# test1.net
KiCad netlist of a schematic drawn in EAGLE
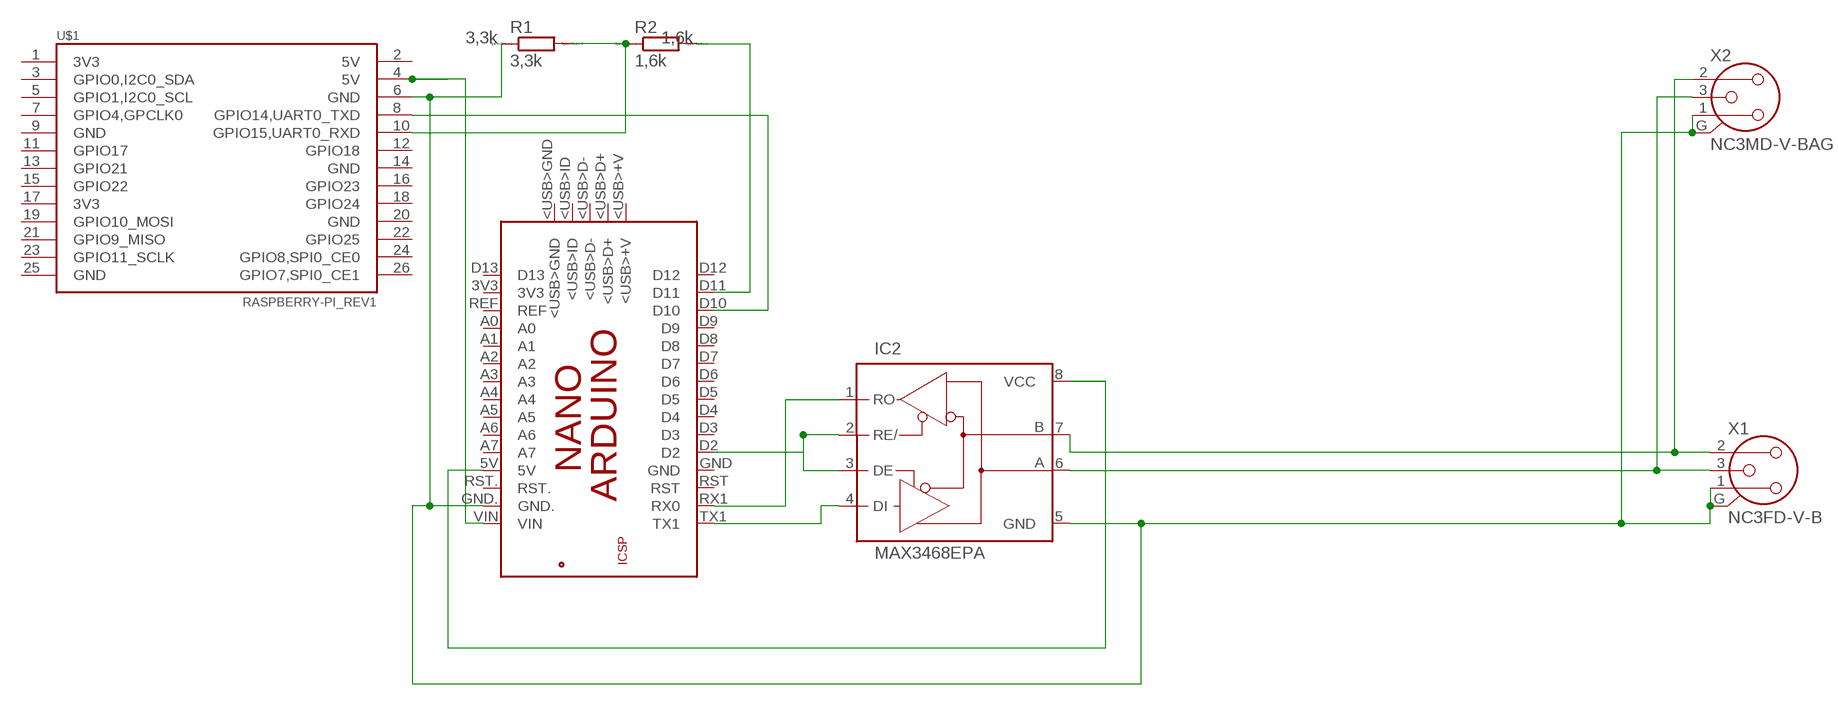
[diagram p0: schematic, sheet 1]

(export (version "E")
  (design (tool "Eeschema 10.0.6"))
  (components
    (comp (ref "IC2")
      (value "MAX3468EPA")
      (footprint "eagle-import:DIL08")
      (fields (field (name "MPN") "MAX3468EPA+"))
      (libsource (lib "eagle-import") (part "MAX34PA68E"))
    )
    (comp (ref "PCB1")
      (value "ARDUINO_NANO")
      (footprint "eagle-import:ARDUINO_NANO")
      (libsource (lib "eagle-import") (part "ARDUINO_NANO"))
    )
    (comp (ref "R1")
      (value "3,3k")
      (footprint "eagle-import:0204_7")
      (fields (field (name "SPICEMODEL") "NONE") (field (name "SPICEMODEL_1") "3,3k"))
      (libsource (lib "eagle-import") (part "R0204/7"))
    )
    (comp (ref "R2")
      (value "1,6k")
      (footprint "eagle-import:0204_7")
      (fields (field (name "SPICEMODEL") "NONE") (field (name "SPICEMODEL_1") "1,6k"))
      (libsource (lib "eagle-import") (part "R0204/7"))
    )
    (comp (ref "U$1")
      (value "RASPBERRY-PI_REV1")
      (footprint "eagle-import:RASPBERRY-PI_REV1")
      (libsource (lib "eagle-import") (part "RASPBERRY-PI_REV1"))
    )
    (comp (ref "X1")
      (value "NC3FD-V-B")
      (footprint "eagle-import:NC3FD-V-B")
      (fields (field (name "MF") "NEUTRIK"))
      (libsource (lib "eagle-import") (part "NC3FD-V-B"))
    )
    (comp (ref "X2")
      (value "NC3MD-V-BAG")
      (footprint "eagle-import:NC3MD-V-BAG")
      (fields (field (name "MF") "NEUTRIK"))
      (libsource (lib "eagle-import") (part "NC3MD-V-BAG"))
    )
  )
  (nets
    (net (code "1") (name "Net-(IC2-A)") (class "Default")
      (node (ref "IC2") (pin "6") (pinfunction "A_6") (pintype "passive"))
      (node (ref "X1") (pin "3") (pinfunction "3_3") (pintype "passive"))
      (node (ref "X2") (pin "3") (pinfunction "3_3") (pintype "passive"))
    )
    (net (code "2") (name "Net-(IC2-B)") (class "Default")
      (node (ref "IC2") (pin "7") (pinfunction "B_7") (pintype "passive"))
      (node (ref "X1") (pin "2") (pinfunction "1_2") (pintype "passive"))
      (node (ref "X2") (pin "2") (pinfunction "1_2") (pintype "passive"))
    )
    (net (code "3") (name "Net-(IC2-DE)") (class "Default")
      (node (ref "IC2") (pin "2") (pinfunction "RE/_2") (pintype "input"))
      (node (ref "IC2") (pin "3") (pinfunction "DE_3") (pintype "input"))
      (node (ref "PCB1") (pin "D2") (pinfunction "D2_D2") (pintype "bidirectional"))
    )
    (net (code "4") (name "Net-(IC2-DI)") (class "Default")
      (node (ref "IC2") (pin "4") (pinfunction "DI_4") (pintype "input"))
      (node (ref "PCB1") (pin "TX1") (pinfunction "TX1_TX1") (pintype "bidirectional"))
    )
    (net (code "5") (name "Net-(IC2-GND)") (class "Default")
      (node (ref "IC2") (pin "5") (pinfunction "GND_5") (pintype "power_in"))
      (node (ref "PCB1") (pin "GND.") (pinfunction "GND._GND.") (pintype "bidirectional"))
      (node (ref "R1") (pin "1") (pinfunction "1_1") (pintype "passive"))
      (node (ref "U$1") (pin "6") (pinfunction "GND_6") (pintype "bidirectional"))
      (node (ref "X1") (pin "1") (pinfunction "2_1") (pintype "passive"))
      (node (ref "X1") (pin "G") (pinfunction "G_G") (pintype "passive"))
      (node (ref "X2") (pin "1") (pinfunction "2_1") (pintype "passive"))
      (node (ref "X2") (pin "G") (pinfunction "G_G") (pintype "passive"))
    )
    (net (code "6") (name "Net-(IC2-RO)") (class "Default")
      (node (ref "IC2") (pin "1") (pinfunction "RO_1") (pintype "output"))
      (node (ref "PCB1") (pin "RX1") (pinfunction "RX0_RX1") (pintype "bidirectional"))
    )
    (net (code "7") (name "Net-(IC2-VCC)") (class "Default")
      (node (ref "IC2") (pin "8") (pinfunction "VCC_8") (pintype "power_in"))
      (node (ref "PCB1") (pin "5V") (pinfunction "5V_5V") (pintype "bidirectional"))
    )
    (net (code "8") (name "Net-(PCB1-PadD11)") (class "Default")
      (node (ref "PCB1") (pin "D11") (pinfunction "D11_D11") (pintype "bidirectional"))
      (node (ref "R2") (pin "2") (pinfunction "2_2") (pintype "passive"))
    )
    (net (code "9") (name "Net-(PCB1-PadVIN)") (class "Default")
      (node (ref "PCB1") (pin "VIN") (pinfunction "VIN_VIN") (pintype "bidirectional"))
      (node (ref "U$1") (pin "4") (pinfunction "5V_4") (pintype "bidirectional"))
    )
    (net (code "10") (name "Net-(U$1-GPIO14,UART0_TXD)") (class "Default")
      (node (ref "PCB1") (pin "D10") (pinfunction "D10_D10") (pintype "bidirectional"))
      (node (ref "U$1") (pin "8") (pinfunction "GPIO14,UART0_TXD_8") (pintype "bidirectional"))
    )
    (net (code "11") (name "Net-(U$1-GPIO15,UART0_RXD)") (class "Default")
      (node (ref "R1") (pin "2") (pinfunction "2_2") (pintype "passive"))
      (node (ref "R2") (pin "1") (pinfunction "1_1") (pintype "passive"))
      (node (ref "U$1") (pin "10") (pinfunction "GPIO15,UART0_RXD_10") (pintype "bidirectional"))
    )
    (net (code "12") (name "unconnected-(PCB1-Pad3V3)") (class "Default")
      (node (ref "PCB1") (pin "3V3") (pinfunction "3V3_3V3") (pintype "bidirectional"))
    )
    (net (code "13") (name "unconnected-(PCB1-Pad5V.)") (class "Default")
      (node (ref "PCB1") (pin "5V.") (pinfunction "5V._5V.") (pintype "bidirectional"))
    )
    (net (code "14") (name "unconnected-(PCB1-Pad<USB>+V)") (class "Default")
      (node (ref "PCB1") (pin "<USB>+V") (pinfunction "<USB>+V_<USB>+V") (pintype "bidirectional"))
    )
    (net (code "15") (name "unconnected-(PCB1-Pad<USB>D+)") (class "Default")
      (node (ref "PCB1") (pin "<USB>D+") (pinfunction "<USB>D+_<USB>D+") (pintype "bidirectional"))
    )
    (net (code "16") (name "unconnected-(PCB1-Pad<USB>D-)") (class "Default")
      (node (ref "PCB1") (pin "<USB>D-") (pinfunction "<USB>D-_<USB>D-") (pintype "bidirectional"))
    )
    (net (code "17") (name "unconnected-(PCB1-Pad<USB>GND)") (class "Default")
      (node (ref "PCB1") (pin "<USB>GND") (pinfunction "<USB>GND_<USB>GND") (pintype "bidirectional"))
    )
    (net (code "18") (name "unconnected-(PCB1-Pad<USB>ID)") (class "Default")
      (node (ref "PCB1") (pin "<USB>ID") (pinfunction "<USB>ID_<USB>ID") (pintype "bidirectional"))
    )
    (net (code "19") (name "unconnected-(PCB1-PadA0)") (class "Default")
      (node (ref "PCB1") (pin "A0") (pinfunction "A0_A0") (pintype "bidirectional"))
    )
    (net (code "20") (name "unconnected-(PCB1-PadA1)") (class "Default")
      (node (ref "PCB1") (pin "A1") (pinfunction "A1_A1") (pintype "bidirectional"))
    )
    (net (code "21") (name "unconnected-(PCB1-PadA2)") (class "Default")
      (node (ref "PCB1") (pin "A2") (pinfunction "A2_A2") (pintype "bidirectional"))
    )
    (net (code "22") (name "unconnected-(PCB1-PadA3)") (class "Default")
      (node (ref "PCB1") (pin "A3") (pinfunction "A3_A3") (pintype "bidirectional"))
    )
    (net (code "23") (name "unconnected-(PCB1-PadA4)") (class "Default")
      (node (ref "PCB1") (pin "A4") (pinfunction "A4_A4") (pintype "bidirectional"))
    )
    (net (code "24") (name "unconnected-(PCB1-PadA5)") (class "Default")
      (node (ref "PCB1") (pin "A5") (pinfunction "A5_A5") (pintype "bidirectional"))
    )
    (net (code "25") (name "unconnected-(PCB1-PadA6)") (class "Default")
      (node (ref "PCB1") (pin "A6") (pinfunction "A6_A6") (pintype "bidirectional"))
    )
    (net (code "26") (name "unconnected-(PCB1-PadA7)") (class "Default")
      (node (ref "PCB1") (pin "A7") (pinfunction "A7_A7") (pintype "bidirectional"))
    )
    (net (code "27") (name "unconnected-(PCB1-PadD3)") (class "Default")
      (node (ref "PCB1") (pin "D3") (pinfunction "D3_D3") (pintype "bidirectional"))
    )
    (net (code "28") (name "unconnected-(PCB1-PadD4)") (class "Default")
      (node (ref "PCB1") (pin "D4") (pinfunction "D4_D4") (pintype "bidirectional"))
    )
    (net (code "29") (name "unconnected-(PCB1-PadD5)") (class "Default")
      (node (ref "PCB1") (pin "D5") (pinfunction "D5_D5") (pintype "bidirectional"))
    )
    (net (code "30") (name "unconnected-(PCB1-PadD6)") (class "Default")
      (node (ref "PCB1") (pin "D6") (pinfunction "D6_D6") (pintype "bidirectional"))
    )
    (net (code "31") (name "unconnected-(PCB1-PadD7)") (class "Default")
      (node (ref "PCB1") (pin "D7") (pinfunction "D7_D7") (pintype "bidirectional"))
    )
    (net (code "32") (name "unconnected-(PCB1-PadD8)") (class "Default")
      (node (ref "PCB1") (pin "D8") (pinfunction "D8_D8") (pintype "bidirectional"))
    )
    (net (code "33") (name "unconnected-(PCB1-PadD9)") (class "Default")
      (node (ref "PCB1") (pin "D9") (pinfunction "D9_D9") (pintype "bidirectional"))
    )
    (net (code "34") (name "unconnected-(PCB1-PadD12)") (class "Default")
      (node (ref "PCB1") (pin "D12") (pinfunction "D12_D12") (pintype "bidirectional"))
    )
    (net (code "35") (name "unconnected-(PCB1-PadD13)") (class "Default")
      (node (ref "PCB1") (pin "D13") (pinfunction "D13_D13") (pintype "bidirectional"))
    )
    (net (code "36") (name "unconnected-(PCB1-PadGND)") (class "Default")
      (node (ref "PCB1") (pin "GND") (pinfunction "GND_GND") (pintype "bidirectional"))
    )
    (net (code "37") (name "unconnected-(PCB1-PadGND_)") (class "Default")
      (node (ref "PCB1") (pin "GND_") (pinfunction "GND__GND_") (pintype "bidirectional"))
    )
    (net (code "38") (name "unconnected-(PCB1-PadMISO)") (class "Default")
      (node (ref "PCB1") (pin "MISO") (pinfunction "MISO_MISO") (pintype "bidirectional"))
    )
    (net (code "39") (name "unconnected-(PCB1-PadMOSI)") (class "Default")
      (node (ref "PCB1") (pin "MOSI") (pinfunction "MOSI_MOSI") (pintype "bidirectional"))
    )
    (net (code "40") (name "unconnected-(PCB1-PadREF)") (class "Default")
      (node (ref "PCB1") (pin "REF") (pinfunction "REF_REF") (pintype "bidirectional"))
    )
    (net (code "41") (name "unconnected-(PCB1-PadRESET..)") (class "Default")
      (node (ref "PCB1") (pin "RESET..") (pinfunction "RESET.._RESET..") (pintype "bidirectional"))
    )
    (net (code "42") (name "unconnected-(PCB1-PadRST)") (class "Default")
      (node (ref "PCB1") (pin "RST") (pinfunction "RST_RST") (pintype "bidirectional"))
    )
    (net (code "43") (name "unconnected-(PCB1-PadRST.)") (class "Default")
      (node (ref "PCB1") (pin "RST.") (pinfunction "RST._RST.") (pintype "bidirectional"))
    )
    (net (code "44") (name "unconnected-(PCB1-PadSCK)") (class "Default")
      (node (ref "PCB1") (pin "SCK") (pinfunction "SCK_SCK") (pintype "bidirectional"))
    )
    (net (code "45") (name "unconnected-(U$1-3V3-Pad1)") (class "Default")
      (node (ref "U$1") (pin "1") (pinfunction "3V3_1") (pintype "bidirectional"))
    )
    (net (code "46") (name "unconnected-(U$1-3V3-Pad17)") (class "Default")
      (node (ref "U$1") (pin "17") (pinfunction "3V3_17") (pintype "bidirectional"))
    )
    (net (code "47") (name "unconnected-(U$1-5V-Pad2)") (class "Default")
      (node (ref "U$1") (pin "2") (pinfunction "5V_2") (pintype "bidirectional"))
    )
    (net (code "48") (name "unconnected-(U$1-GND-Pad9)") (class "Default")
      (node (ref "U$1") (pin "9") (pinfunction "GND_9") (pintype "bidirectional"))
    )
    (net (code "49") (name "unconnected-(U$1-GND-Pad14)") (class "Default")
      (node (ref "U$1") (pin "14") (pinfunction "GND_14") (pintype "bidirectional"))
    )
    (net (code "50") (name "unconnected-(U$1-GND-Pad20)") (class "Default")
      (node (ref "U$1") (pin "20") (pinfunction "GND_20") (pintype "bidirectional"))
    )
    (net (code "51") (name "unconnected-(U$1-GND-Pad25)") (class "Default")
      (node (ref "U$1") (pin "25") (pinfunction "GND_25") (pintype "bidirectional"))
    )
    (net (code "52") (name "unconnected-(U$1-GPIO0,I2C0_SDA-Pad3)") (class "Default")
      (node (ref "U$1") (pin "3") (pinfunction "GPIO0,I2C0_SDA_3") (pintype "bidirectional"))
    )
    (net (code "53") (name "unconnected-(U$1-GPIO1,I2C0_SCL-Pad5)") (class "Default")
      (node (ref "U$1") (pin "5") (pinfunction "GPIO1,I2C0_SCL_5") (pintype "bidirectional"))
    )
    (net (code "54") (name "unconnected-(U$1-GPIO4,GPCLK0-Pad7)") (class "Default")
      (node (ref "U$1") (pin "7") (pinfunction "GPIO4,GPCLK0_7") (pintype "bidirectional"))
    )
    (net (code "55") (name "unconnected-(U$1-GPIO7,SPI0_CE1-Pad26)") (class "Default")
      (node (ref "U$1") (pin "26") (pinfunction "GPIO7,SPI0_CE1_26") (pintype "bidirectional"))
    )
    (net (code "56") (name "unconnected-(U$1-GPIO8,SPI0_CE0-Pad24)") (class "Default")
      (node (ref "U$1") (pin "24") (pinfunction "GPIO8,SPI0_CE0_24") (pintype "bidirectional"))
    )
    (net (code "57") (name "unconnected-(U$1-GPIO9_MISO-Pad21)") (class "Default")
      (node (ref "U$1") (pin "21") (pinfunction "GPIO9_MISO_21") (pintype "bidirectional"))
    )
    (net (code "58") (name "unconnected-(U$1-GPIO10_MOSI-Pad19)") (class "Default")
      (node (ref "U$1") (pin "19") (pinfunction "GPIO10_MOSI_19") (pintype "bidirectional"))
    )
    (net (code "59") (name "unconnected-(U$1-GPIO11_SCLK-Pad23)") (class "Default")
      (node (ref "U$1") (pin "23") (pinfunction "GPIO11_SCLK_23") (pintype "bidirectional"))
    )
    (net (code "60") (name "unconnected-(U$1-GPIO17-Pad11)") (class "Default")
      (node (ref "U$1") (pin "11") (pinfunction "GPIO17_11") (pintype "bidirectional"))
    )
    (net (code "61") (name "unconnected-(U$1-GPIO18-Pad12)") (class "Default")
      (node (ref "U$1") (pin "12") (pinfunction "GPIO18_12") (pintype "bidirectional"))
    )
    (net (code "62") (name "unconnected-(U$1-GPIO21-Pad13)") (class "Default")
      (node (ref "U$1") (pin "13") (pinfunction "GPIO21_13") (pintype "bidirectional"))
    )
    (net (code "63") (name "unconnected-(U$1-GPIO22-Pad15)") (class "Default")
      (node (ref "U$1") (pin "15") (pinfunction "GPIO22_15") (pintype "bidirectional"))
    )
    (net (code "64") (name "unconnected-(U$1-GPIO23-Pad16)") (class "Default")
      (node (ref "U$1") (pin "16") (pinfunction "GPIO23_16") (pintype "bidirectional"))
    )
    (net (code "65") (name "unconnected-(U$1-GPIO24-Pad18)") (class "Default")
      (node (ref "U$1") (pin "18") (pinfunction "GPIO24_18") (pintype "bidirectional"))
    )
    (net (code "66") (name "unconnected-(U$1-GPIO25-Pad22)") (class "Default")
      (node (ref "U$1") (pin "22") (pinfunction "GPIO25_22") (pintype "bidirectional"))
    )
  )
)
